# ExtFlash.net
KiCad netlist of a schematic drawn in Altium Designer
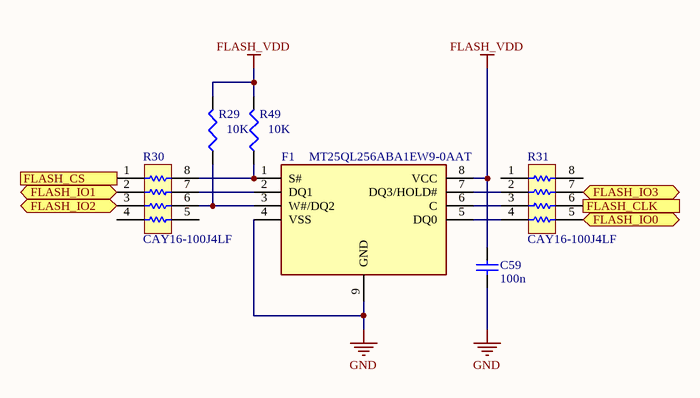
[diagram p0: ExtFlash.SchDoc]

(export (version "E")
  (design (tool "Eeschema 10.0.6"))
  (components
    (comp (ref "C59")
      (value "100n")
      (footprint "CAPC1608X90X35NL10T15")
      (fields (field (name "PART NUMBER") "GRM188R71H102KA01D") (field (name "MANUFACTURER") "Murata"))
      (libsource (lib "Altium Content Vault") (part "CAP"))
    )
    (comp (ref "F1")
      (value "MT25QL256ABA1EW9-0AAT")
      (footprint "SamacSys:SON127P800X600X80-9N-D")
      (description "Integrated Circuit")
      (fields (field (name "MOUSER PART NUMBER") "340-322381-TRAY"))
      (libsource (lib "*") (part "MT25QL256ABA1EW9-0AAT"))
    )
    (comp (ref "R29")
      (value "10K")
      (footprint "J1-0603")
      (description "Resistor")
      (fields (field (name "PUBLISHER") "Altium Limited"))
      (libsource (lib "Miscellaneous Devices") (part "Res3"))
    )
    (comp (ref "R30")
      (value "CAY16-100J4LF")
      (footprint "BOUR-CAY16-J4_V")
      (description "Chip Resistor Array, 1 KOhm, +/- 5%, 62.5 mW, -55 to 125 degC, 8-Pin SMD, RoHS, Tape and Reel")
      (fields (field (name "TOLERANCE") "1%"))
      (libsource (lib "Altium Content Vault") (part "RES-P-8"))
    )
    (comp (ref "R31")
      (value "CAY16-100J4LF")
      (footprint "BOUR-CAY16-J4_V")
      (description "Chip Resistor Array, 1 KOhm, +/- 5%, 62.5 mW, -55 to 125 degC, 8-Pin SMD, RoHS, Tape and Reel")
      (fields (field (name "TOLERANCE") "1%"))
      (libsource (lib "Altium Content Vault") (part "RES-P-8"))
    )
    (comp (ref "R49")
      (value "10K")
      (footprint "J1-0603")
      (description "Resistor")
      (fields (field (name "PUBLISHER") "Altium Limited"))
      (libsource (lib "Miscellaneous Devices") (part "Res3"))
    )
  )
  (nets
    (net (code "1") (name "/FLASH_CLK") (class "Default")
      (node (ref "R31") (pin "6") (pinfunction "6_6") (pintype "passive"))
    )
    (net (code "2") (name "/FLASH_CS") (class "Default")
      (node (ref "R30") (pin "1") (pinfunction "1_1") (pintype "passive"))
    )
    (net (code "3") (name "/FLASH_IO0") (class "Default")
      (node (ref "R31") (pin "5") (pinfunction "5_5") (pintype "passive"))
    )
    (net (code "4") (name "/FLASH_IO1") (class "Default")
      (node (ref "R30") (pin "2") (pinfunction "2_2") (pintype "passive"))
    )
    (net (code "5") (name "/FLASH_IO2") (class "Default")
      (node (ref "R30") (pin "3") (pinfunction "3_3") (pintype "passive"))
    )
    (net (code "6") (name "/FLASH_IO3") (class "Default")
      (node (ref "R31") (pin "7") (pinfunction "7_7") (pintype "passive"))
    )
    (net (code "7") (name "FLASH_VDD") (class "Default")
      (node (ref "C59") (pin "2") (pinfunction "2_2") (pintype "passive"))
      (node (ref "F1") (pin "8") (pinfunction "VCC_8") (pintype "passive"))
      (node (ref "R29") (pin "2") (pinfunction "2_2") (pintype "passive"))
      (node (ref "R49") (pin "2") (pinfunction "2_2") (pintype "passive"))
    )
    (net (code "8") (name "GND") (class "Default")
      (node (ref "C59") (pin "1") (pinfunction "1_1") (pintype "passive"))
      (node (ref "F1") (pin "4") (pinfunction "VSS_4") (pintype "passive"))
      (node (ref "F1") (pin "9") (pinfunction "GND_9") (pintype "passive"))
    )
    (net (code "9") (name "Net-(F1-C)") (class "Default")
      (node (ref "F1") (pin "6") (pinfunction "C_6") (pintype "passive"))
      (node (ref "R31") (pin "3") (pinfunction "3_3") (pintype "passive"))
    )
    (net (code "10") (name "Net-(F1-DQ0)") (class "Default")
      (node (ref "F1") (pin "5") (pinfunction "DQ0_5") (pintype "passive"))
      (node (ref "R31") (pin "4") (pinfunction "4_4") (pintype "passive"))
    )
    (net (code "11") (name "Net-(F1-DQ1)") (class "Default")
      (node (ref "F1") (pin "2") (pinfunction "DQ1_2") (pintype "passive"))
      (node (ref "R30") (pin "7") (pinfunction "7_7") (pintype "passive"))
    )
    (net (code "12") (name "Net-(F1-DQ3{slash}HOLD#)") (class "Default")
      (node (ref "F1") (pin "7") (pinfunction "DQ3/HOLD#_7") (pintype "passive"))
      (node (ref "R31") (pin "2") (pinfunction "2_2") (pintype "passive"))
    )
    (net (code "13") (name "Net-(F1-S#)") (class "Default")
      (node (ref "F1") (pin "1") (pinfunction "S#_1") (pintype "passive"))
      (node (ref "R30") (pin "8") (pinfunction "8_8") (pintype "passive"))
      (node (ref "R49") (pin "1") (pinfunction "1_1") (pintype "passive"))
    )
    (net (code "14") (name "Net-(F1-W#{slash}DQ2)") (class "Default")
      (node (ref "F1") (pin "3") (pinfunction "W#/DQ2_3") (pintype "passive"))
      (node (ref "R29") (pin "1") (pinfunction "1_1") (pintype "passive"))
      (node (ref "R30") (pin "6") (pinfunction "6_6") (pintype "passive"))
    )
    (net (code "15") (name "unconnected-(R30-Pad4)") (class "Default")
      (node (ref "R30") (pin "4") (pinfunction "4_4") (pintype "passive"))
    )
    (net (code "16") (name "unconnected-(R30-Pad5)") (class "Default")
      (node (ref "R30") (pin "5") (pinfunction "5_5") (pintype "passive"))
    )
    (net (code "17") (name "unconnected-(R31-Pad1)") (class "Default")
      (node (ref "R31") (pin "1") (pinfunction "1_1") (pintype "passive"))
    )
    (net (code "18") (name "unconnected-(R31-Pad8)") (class "Default")
      (node (ref "R31") (pin "8") (pinfunction "8_8") (pintype "passive"))
    )
  )
)
